# keyboard.net
KiCad netlist of a schematic drawn in EAGLE
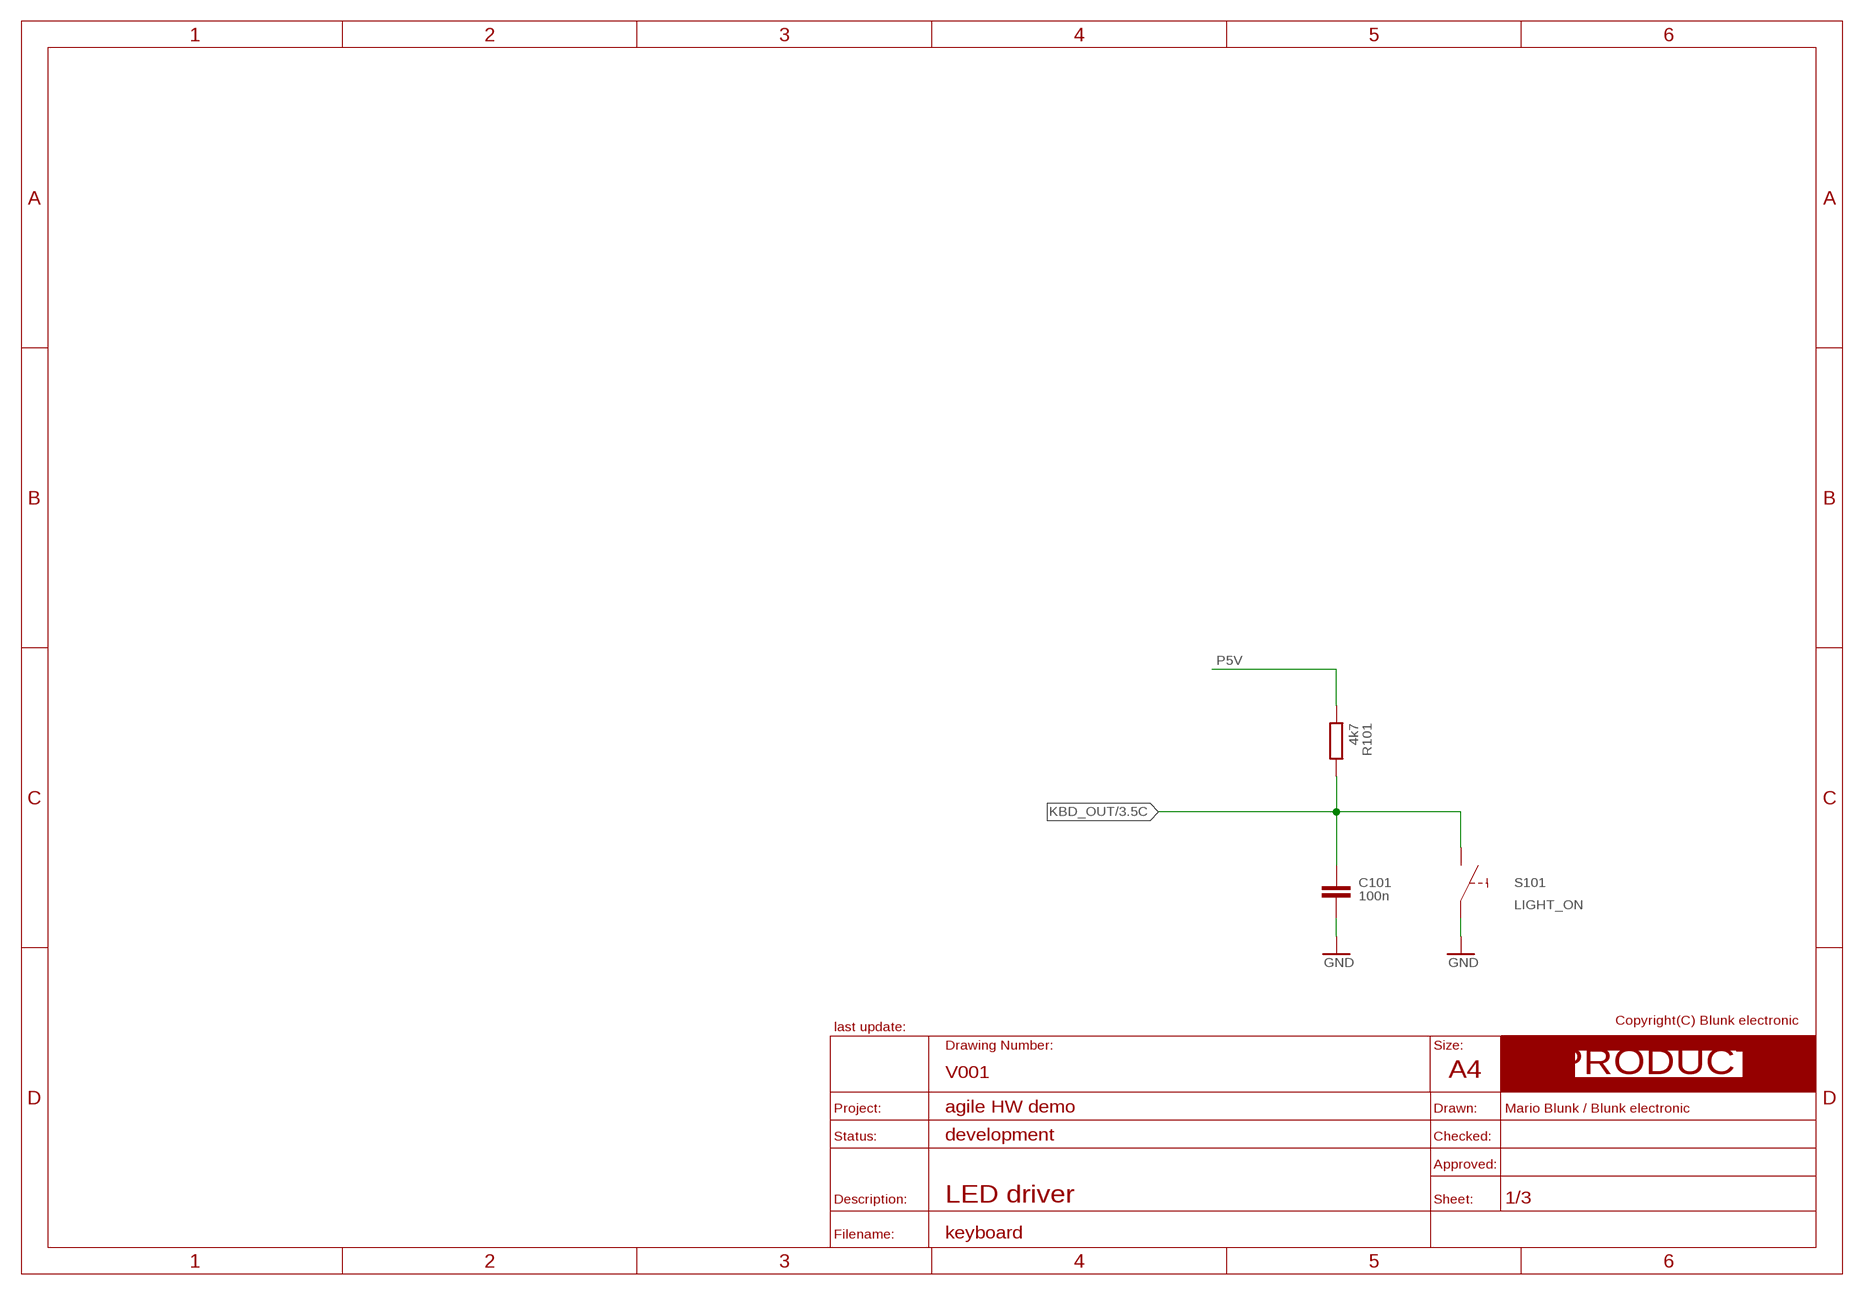
[diagram p0: schematic, sheet 1]
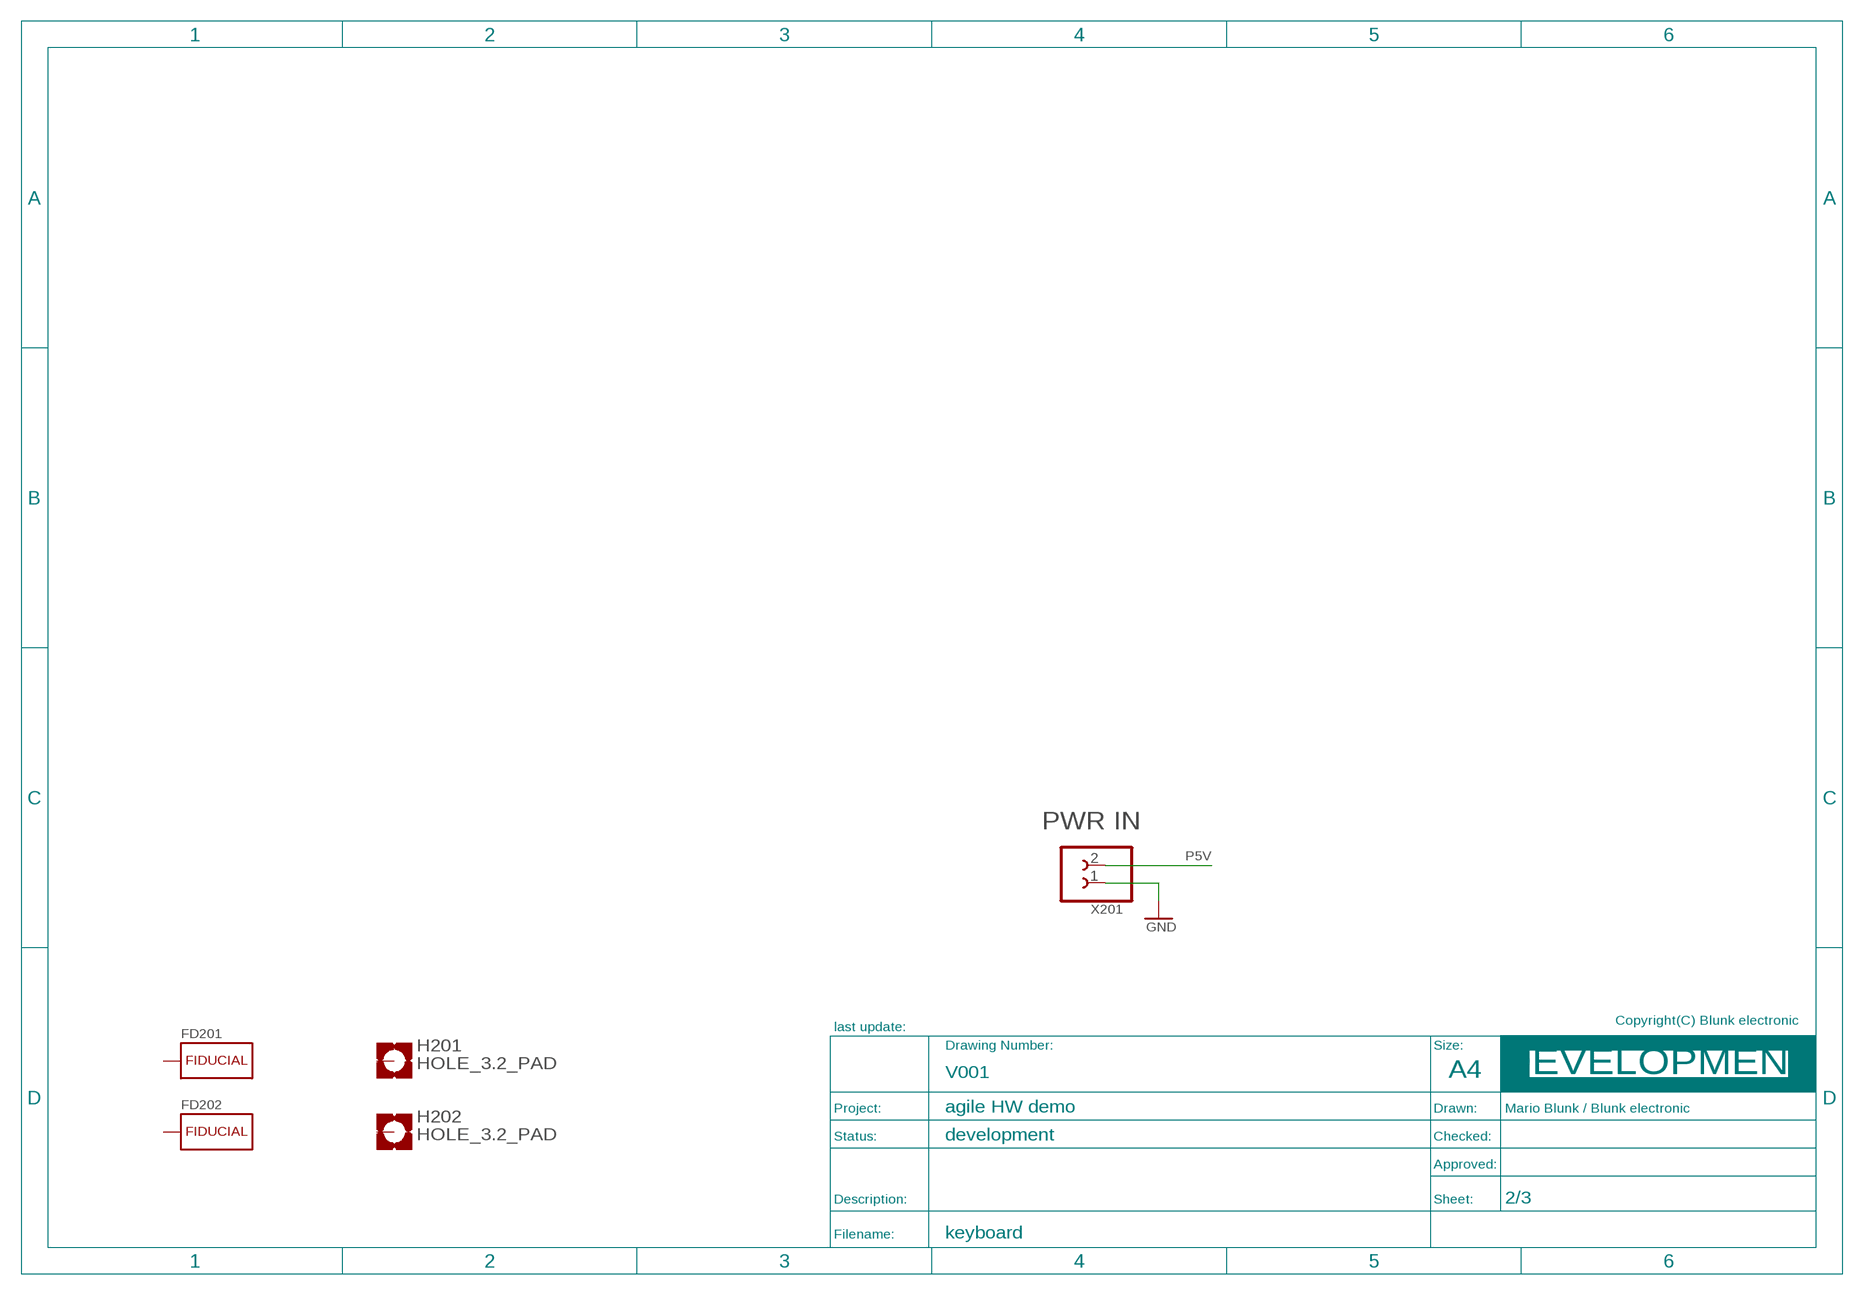
[diagram p1: schematic, sheet 2]
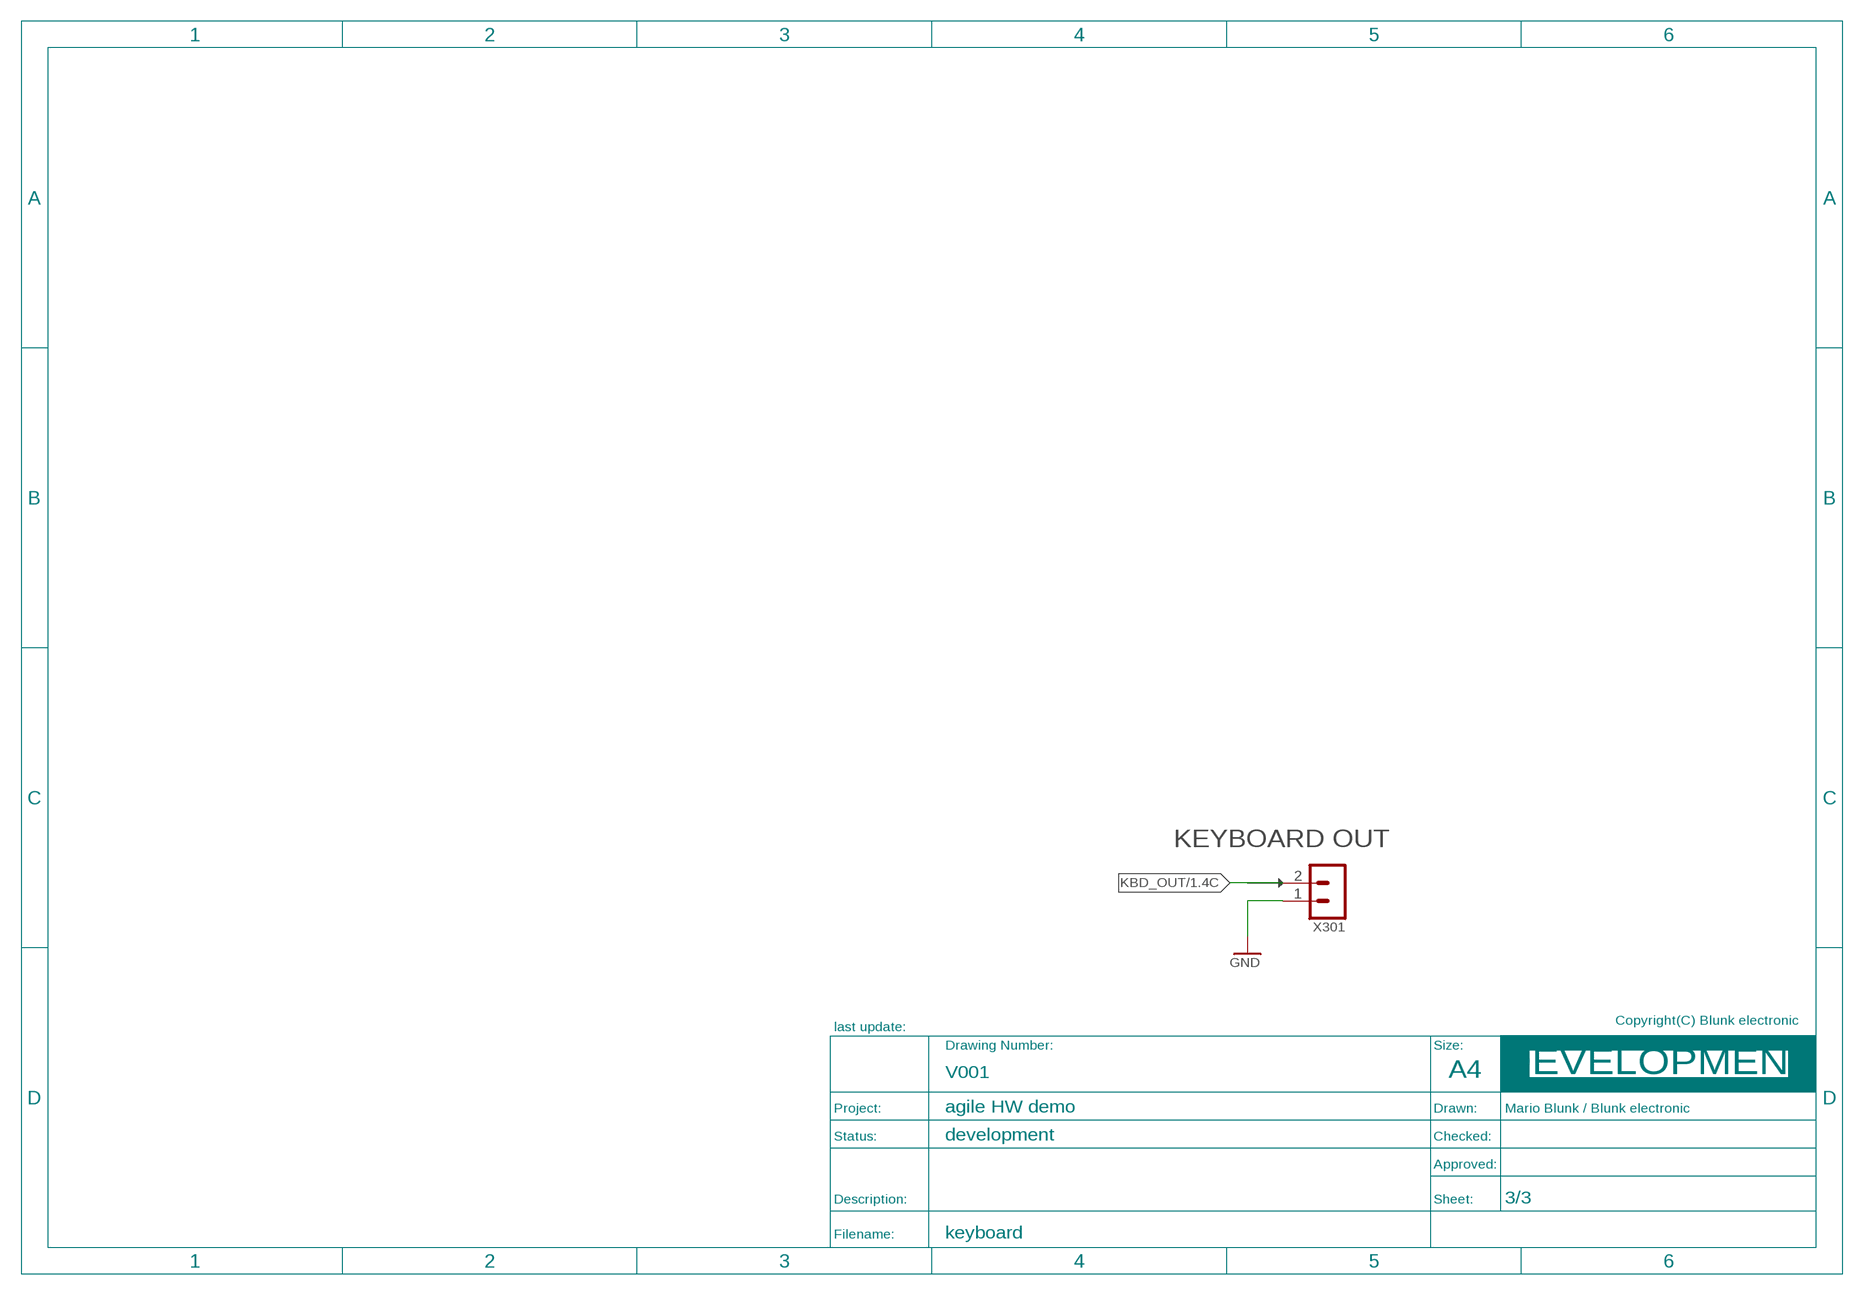
[diagram p2: schematic, sheet 3]

(export (version "E")
  (design (tool "Eeschema 10.0.6"))
  (components
    (comp (ref "C101")
      (value "100n")
      (footprint "eagle-import:S_0805")
      (fields (field (name "PART_CODE_BEL") "C_PAC_S_0805_VAL_100n"))
      (libsource (lib "eagle-import") (part "C_S_0805"))
    )
    (comp (ref "R101")
      (value "4k7")
      (footprint "eagle-import:S_0805")
      (fields (field (name "PART_CODE_BEL") "R_PAC_S_0805_VAL_4k7"))
      (libsource (lib "eagle-import") (part "R_S_0805"))
    )
    (comp (ref "S101")
      (value "PUSH_BUTTON_S_6X6MM")
      (footprint "eagle-import:S_PUSH_BUTTON_6X6")
      (fields (field (name "FUNCTION") "LIGHT_ON") (field (name "PART_CODE_BEL") "S_PAC_S_PUSH_BUTTON_6X6"))
      (libsource (lib "eagle-import") (part "PUSH_BUTTON_S_6X6MM"))
    )
    (comp (ref "X301")
      (value "MALE_2X1-T-VERTICAL")
      (footprint "eagle-import:T_MALE_2X1_VERTICAL_PITCH_2MM54")
      (fields (field (name "FUNCTION") "KEYBOARD OUT"))
      (libsource (lib "eagle-import") (part "MALE_2X1-T-VERTICAL"))
    )
    (comp (ref "FD201")
      (value "FIDUCIAL_CROSSHAIR")
      (footprint "eagle-import:CROSSHAIR")
      (libsource (lib "eagle-import") (part "FIDUCIAL_CROSSHAIR"))
    )
    (comp (ref "FD202")
      (value "FIDUCIAL_CROSSHAIR")
      (footprint "eagle-import:CROSSHAIR")
      (libsource (lib "eagle-import") (part "FIDUCIAL_CROSSHAIR"))
    )
    (comp (ref "H201")
      (value "HOLE_3.2_PAD")
      (footprint "eagle-import:3.2_PAD")
      (libsource (lib "eagle-import") (part "HOLE_3.2_PAD"))
    )
    (comp (ref "H202")
      (value "HOLE_3.2_PAD")
      (footprint "eagle-import:3.2_PAD")
      (libsource (lib "eagle-import") (part "HOLE_3.2_PAD"))
    )
    (comp (ref "X201")
      (value "CLAMP_1X2-T-2.5MM")
      (footprint "eagle-import:T_WIRE_CLAMP_1X2_PITCH_2MM5")
      (fields (field (name "FUNCTION") "PWR IN"))
      (libsource (lib "eagle-import") (part "CLAMP_1X2-T-2.5MM"))
    )
  )
  (nets
    (net (code "1") (name "GND") (class "Default")
      (node (ref "C101") (pin "2") (pinfunction "2_2") (pintype "passive"))
      (node (ref "S101") (pin "A") (pinfunction "A1_A") (pintype "passive"))
      (node (ref "S101") (pin "A1") (pinfunction "A1_A1") (pintype "passive"))
      (node (ref "X201") (pin "1") (pinfunction "1_1") (pintype "passive"))
      (node (ref "X301") (pin "1") (pinfunction "1_1") (pintype "passive"))
    )
    (net (code "2") (name "KBD_OUT") (class "Default")
      (node (ref "C101") (pin "1") (pinfunction "1_1") (pintype "passive"))
      (node (ref "R101") (pin "2") (pinfunction "2_2") (pintype "passive"))
      (node (ref "S101") (pin "B") (pinfunction "B1_B") (pintype "passive"))
      (node (ref "S101") (pin "B1") (pinfunction "B1_B1") (pintype "passive"))
      (node (ref "X301") (pin "2") (pinfunction "2_2") (pintype "passive"))
    )
    (net (code "3") (name "P5V") (class "Default")
      (node (ref "R101") (pin "1") (pinfunction "1_1") (pintype "passive"))
      (node (ref "X201") (pin "2") (pinfunction "2_2") (pintype "passive"))
    )
    (net (code "4") (name "unconnected-(FD201-NC-Pad1)") (class "Default")
      (node (ref "FD201") (pin "1") (pinfunction "NC_1") (pintype "no_connect"))
    )
    (net (code "5") (name "unconnected-(FD202-NC-Pad1)") (class "Default")
      (node (ref "FD202") (pin "1") (pinfunction "NC_1") (pintype "no_connect"))
    )
    (net (code "6") (name "unconnected-(H201-MOUNT-PadH1)") (class "Default")
      (node (ref "H201") (pin "H1") (pinfunction "MOUNT_H1") (pintype "passive"))
    )
    (net (code "7") (name "unconnected-(H202-MOUNT-PadH1)") (class "Default")
      (node (ref "H202") (pin "H1") (pinfunction "MOUNT_H1") (pintype "passive"))
    )
  )
)
